# CR78-MB.net
KiCad netlist of a schematic drawn in EAGLE
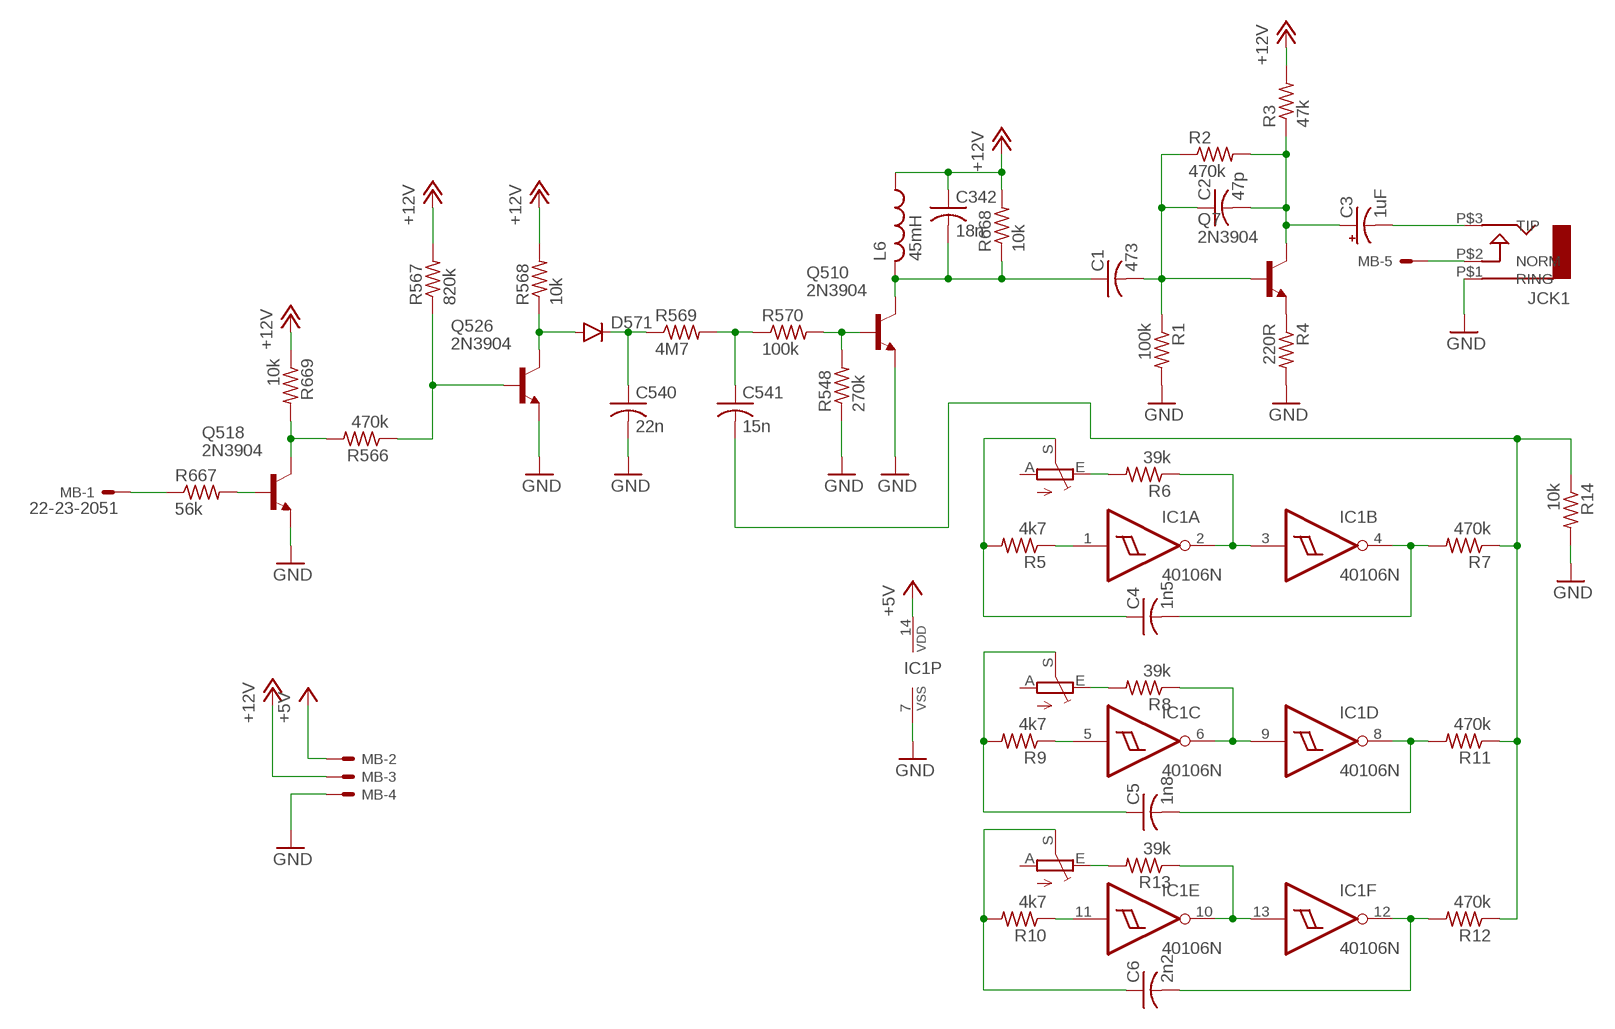
[diagram p0: schematic, sheet 1]

(export (version "E")
  (design (tool "Eeschema 10.0.6"))
  (components
    (comp (ref "C1")
      (value "473")
      (footprint "eagle-import:C050-025X075")
      (libsource (lib "eagle-import") (part "C-US050-025X075"))
    )
    (comp (ref "C2")
      (value "47p")
      (footprint "eagle-import:C025-030X050")
      (libsource (lib "eagle-import") (part "C-US025-030X050"))
    )
    (comp (ref "C3")
      (value "1uF")
      (footprint "eagle-import:B45181B")
      (libsource (lib "eagle-import") (part "CPOL-USB45181B"))
    )
    (comp (ref "C4")
      (value "1n5")
      (footprint "eagle-import:C050-025X075")
      (libsource (lib "eagle-import") (part "C-US050-025X075"))
    )
    (comp (ref "C5")
      (value "1n8")
      (footprint "eagle-import:C050-025X075")
      (libsource (lib "eagle-import") (part "C-US050-025X075"))
    )
    (comp (ref "C6")
      (value "2n2")
      (footprint "eagle-import:C050-025X075")
      (libsource (lib "eagle-import") (part "C-US050-025X075"))
    )
    (comp (ref "C342")
      (value "18n")
      (footprint "eagle-import:C050-025X075")
      (libsource (lib "eagle-import") (part "C-US050-025X075"))
    )
    (comp (ref "C540")
      (value "22n")
      (footprint "eagle-import:C050-025X075")
      (libsource (lib "eagle-import") (part "C-US050-025X075"))
    )
    (comp (ref "C541")
      (value "15n")
      (footprint "eagle-import:C050-025X075")
      (libsource (lib "eagle-import") (part "C-US050-025X075"))
    )
    (comp (ref "D571")
      (value "DIODE1N4148")
      (footprint "eagle-import:DIODE-1N4148")
      (libsource (lib "eagle-import") (part "DIODE1N4148"))
    )
    (comp (ref "IC1")
      (value "40106N")
      (footprint "eagle-import:DIL14")
      (libsource (lib "eagle-import") (part "40106N"))
    )
    (comp (ref "JCK1")
      (value "AUDIO-JACK")
      (footprint "eagle-import:ERTHENVAR-JACK-90DEG")
      (libsource (lib "eagle-import") (part "AUDIO-JACK"))
    )
    (comp (ref "L6")
      (value "45mH")
      (footprint "eagle-import:0204_5")
      (libsource (lib "eagle-import") (part "L-US0204/5"))
    )
    (comp (ref "MB")
      (value "22-23-2051")
      (footprint "eagle-import:22-23-2051")
      (fields (field (name "MF") "MOLEX"))
      (libsource (lib "eagle-import") (part "22-23-2051"))
    )
    (comp (ref "Q7")
      (value "2N3904")
      (footprint "eagle-import:TO92")
      (libsource (lib "eagle-import") (part "2N3904"))
    )
    (comp (ref "Q510")
      (value "2N3904")
      (footprint "eagle-import:TO92")
      (libsource (lib "eagle-import") (part "2N3904"))
    )
    (comp (ref "Q518")
      (value "2N3904")
      (footprint "eagle-import:TO92")
      (libsource (lib "eagle-import") (part "2N3904"))
    )
    (comp (ref "Q526")
      (value "2N3904")
      (footprint "eagle-import:TO92")
      (libsource (lib "eagle-import") (part "2N3904"))
    )
    (comp (ref "R1")
      (value "100k")
      (footprint "eagle-import:0207_7")
      (libsource (lib "eagle-import") (part "R-US_0207/7"))
    )
    (comp (ref "R2")
      (value "470k")
      (footprint "eagle-import:0207_7")
      (libsource (lib "eagle-import") (part "R-US_0207/7"))
    )
    (comp (ref "R3")
      (value "47k")
      (footprint "eagle-import:0207_7")
      (libsource (lib "eagle-import") (part "R-US_0207/7"))
    )
    (comp (ref "R4")
      (value "220R")
      (footprint "eagle-import:0207_7")
      (libsource (lib "eagle-import") (part "R-US_0207/7"))
    )
    (comp (ref "R5")
      (value "4k7")
      (footprint "eagle-import:0207_7")
      (libsource (lib "eagle-import") (part "R-US_0207/7"))
    )
    (comp (ref "R6")
      (value "39k")
      (footprint "eagle-import:0207_7")
      (libsource (lib "eagle-import") (part "R-US_0207/7"))
    )
    (comp (ref "R7")
      (value "470k")
      (footprint "eagle-import:0207_7")
      (libsource (lib "eagle-import") (part "R-US_0207/7"))
    )
    (comp (ref "R8")
      (value "39k")
      (footprint "eagle-import:0207_7")
      (libsource (lib "eagle-import") (part "R-US_0207/7"))
    )
    (comp (ref "R9")
      (value "4k7")
      (footprint "eagle-import:0207_7")
      (libsource (lib "eagle-import") (part "R-US_0207/7"))
    )
    (comp (ref "R10")
      (value "4k7")
      (footprint "eagle-import:0207_7")
      (libsource (lib "eagle-import") (part "R-US_0207/7"))
    )
    (comp (ref "R11")
      (value "470k")
      (footprint "eagle-import:0207_7")
      (libsource (lib "eagle-import") (part "R-US_0207/7"))
    )
    (comp (ref "R12")
      (value "470k")
      (footprint "eagle-import:0207_7")
      (libsource (lib "eagle-import") (part "R-US_0207/7"))
    )
    (comp (ref "R13")
      (value "39k")
      (footprint "eagle-import:0207_7")
      (libsource (lib "eagle-import") (part "R-US_0207/7"))
    )
    (comp (ref "R14")
      (value "10k")
      (footprint "eagle-import:0207_7")
      (libsource (lib "eagle-import") (part "R-US_0207/7"))
    )
    (comp (ref "R548")
      (value "270k")
      (footprint "eagle-import:0207_7")
      (libsource (lib "eagle-import") (part "R-US_0207/7"))
    )
    (comp (ref "R566")
      (value "470k")
      (footprint "eagle-import:0207_7")
      (libsource (lib "eagle-import") (part "R-US_0207/7"))
    )
    (comp (ref "R567")
      (value "820k")
      (footprint "eagle-import:0207_7")
      (libsource (lib "eagle-import") (part "R-US_0207/7"))
    )
    (comp (ref "R568")
      (value "10k")
      (footprint "eagle-import:0207_7")
      (libsource (lib "eagle-import") (part "R-US_0207/7"))
    )
    (comp (ref "R569")
      (value "4M7")
      (footprint "eagle-import:0207_7")
      (libsource (lib "eagle-import") (part "R-US_0207/7"))
    )
    (comp (ref "R570")
      (value "100k")
      (footprint "eagle-import:0207_7")
      (libsource (lib "eagle-import") (part "R-US_0207/7"))
    )
    (comp (ref "R667")
      (value "56k")
      (footprint "eagle-import:0207_7")
      (libsource (lib "eagle-import") (part "R-US_0207/7"))
    )
    (comp (ref "R668")
      (value "10k")
      (footprint "eagle-import:0207_7")
      (libsource (lib "eagle-import") (part "R-US_0207/7"))
    )
    (comp (ref "R669")
      (value "10k")
      (footprint "eagle-import:0207_7")
      (libsource (lib "eagle-import") (part "R-US_0207/7"))
    )
    (comp (ref "VR1")
      (value "20K")
      (footprint "eagle-import:B64Y")
      (libsource (lib "eagle-import") (part "TRIM_EU-B64Y"))
    )
    (comp (ref "VR2")
      (value "20K")
      (footprint "eagle-import:B64Y")
      (libsource (lib "eagle-import") (part "TRIM_EU-B64Y"))
    )
    (comp (ref "VR3")
      (value "20K")
      (footprint "eagle-import:B64Y")
      (libsource (lib "eagle-import") (part "TRIM_EU-B64Y"))
    )
  )
  (nets
    (net (code "1") (name "+5V") (class "Default")
      (node (ref "IC1") (pin "14") (pinfunction "VDD_14") (pintype "power_in"))
      (node (ref "MB") (pin "2") (pinfunction "S_2") (pintype "passive"))
    )
    (net (code "2") (name "+12V") (class "Default")
      (node (ref "C342") (pin "1") (pinfunction "1_1") (pintype "passive"))
      (node (ref "L6") (pin "1") (pinfunction "1_1") (pintype "passive"))
      (node (ref "MB") (pin "3") (pinfunction "S_3") (pintype "passive"))
      (node (ref "R3") (pin "2") (pinfunction "2_2") (pintype "passive"))
      (node (ref "R567") (pin "2") (pinfunction "2_2") (pintype "passive"))
      (node (ref "R568") (pin "2") (pinfunction "2_2") (pintype "passive"))
      (node (ref "R668") (pin "2") (pinfunction "2_2") (pintype "passive"))
      (node (ref "R669") (pin "1") (pinfunction "1_1") (pintype "passive"))
    )
    (net (code "3") (name "GND") (class "Default")
      (node (ref "C540") (pin "2") (pinfunction "2_2") (pintype "passive"))
      (node (ref "IC1") (pin "7") (pinfunction "VSS_7") (pintype "power_in"))
      (node (ref "JCK1") (pin "P$1") (pinfunction "RING_P$1") (pintype "bidirectional"))
      (node (ref "MB") (pin "4") (pinfunction "S_4") (pintype "passive"))
      (node (ref "Q510") (pin "3") (pinfunction "E_3") (pintype "passive"))
      (node (ref "Q518") (pin "3") (pinfunction "E_3") (pintype "passive"))
      (node (ref "Q526") (pin "3") (pinfunction "E_3") (pintype "passive"))
      (node (ref "R1") (pin "2") (pinfunction "2_2") (pintype "passive"))
      (node (ref "R14") (pin "2") (pinfunction "2_2") (pintype "passive"))
      (node (ref "R4") (pin "2") (pinfunction "2_2") (pintype "passive"))
      (node (ref "R548") (pin "1") (pinfunction "1_1") (pintype "passive"))
    )
    (net (code "4") (name "Net-(C4-Pad1)") (class "Default")
      (node (ref "C4") (pin "1") (pinfunction "1_1") (pintype "passive"))
      (node (ref "R5") (pin "2") (pinfunction "2_2") (pintype "passive"))
      (node (ref "VR1") (pin "S") (pinfunction "S_S") (pintype "passive"))
    )
    (net (code "5") (name "Net-(C5-Pad1)") (class "Default")
      (node (ref "C5") (pin "1") (pinfunction "1_1") (pintype "passive"))
      (node (ref "R9") (pin "2") (pinfunction "2_2") (pintype "passive"))
      (node (ref "VR2") (pin "S") (pinfunction "S_S") (pintype "passive"))
    )
    (net (code "6") (name "Net-(C6-Pad1)") (class "Default")
      (node (ref "C6") (pin "1") (pinfunction "1_1") (pintype "passive"))
      (node (ref "R10") (pin "2") (pinfunction "2_2") (pintype "passive"))
      (node (ref "VR3") (pin "S") (pinfunction "S_S") (pintype "passive"))
    )
    (net (code "7") (name "Net-(C540-Pad1)") (class "Default")
      (node (ref "C540") (pin "1") (pinfunction "1_1") (pintype "passive"))
      (node (ref "D571") (pin "C") (pinfunction "C_C") (pintype "passive"))
      (node (ref "R569") (pin "1") (pinfunction "1_1") (pintype "passive"))
    )
    (net (code "8") (name "Net-(C541-Pad1)") (class "Default")
      (node (ref "C541") (pin "1") (pinfunction "1_1") (pintype "passive"))
      (node (ref "R569") (pin "2") (pinfunction "2_2") (pintype "passive"))
      (node (ref "R570") (pin "1") (pinfunction "1_1") (pintype "passive"))
    )
    (net (code "9") (name "Net-(C541-Pad2)") (class "Default")
      (node (ref "C541") (pin "2") (pinfunction "2_2") (pintype "passive"))
      (node (ref "R11") (pin "1") (pinfunction "1_1") (pintype "passive"))
      (node (ref "R12") (pin "1") (pinfunction "1_1") (pintype "passive"))
      (node (ref "R14") (pin "1") (pinfunction "1_1") (pintype "passive"))
      (node (ref "R7") (pin "1") (pinfunction "1_1") (pintype "passive"))
    )
    (net (code "10") (name "Net-(IC1A-I)") (class "Default")
      (node (ref "IC1") (pin "1") (pinfunction "I_1") (pintype "input"))
      (node (ref "R5") (pin "1") (pinfunction "1_1") (pintype "passive"))
    )
    (net (code "11") (name "Net-(IC1A-O)") (class "Default")
      (node (ref "IC1") (pin "2") (pinfunction "O_2") (pintype "output"))
      (node (ref "IC1") (pin "3") (pinfunction "I_3") (pintype "input"))
      (node (ref "R6") (pin "1") (pinfunction "1_1") (pintype "passive"))
    )
    (net (code "12") (name "Net-(IC1B-O)") (class "Default")
      (node (ref "C4") (pin "2") (pinfunction "2_2") (pintype "passive"))
      (node (ref "IC1") (pin "4") (pinfunction "O_4") (pintype "output"))
      (node (ref "R7") (pin "2") (pinfunction "2_2") (pintype "passive"))
    )
    (net (code "13") (name "Net-(IC1C-I)") (class "Default")
      (node (ref "IC1") (pin "5") (pinfunction "I_5") (pintype "input"))
      (node (ref "R9") (pin "1") (pinfunction "1_1") (pintype "passive"))
    )
    (net (code "14") (name "Net-(IC1C-O)") (class "Default")
      (node (ref "IC1") (pin "6") (pinfunction "O_6") (pintype "output"))
      (node (ref "IC1") (pin "9") (pinfunction "I_9") (pintype "input"))
      (node (ref "R8") (pin "1") (pinfunction "1_1") (pintype "passive"))
    )
    (net (code "15") (name "Net-(IC1D-O)") (class "Default")
      (node (ref "C5") (pin "2") (pinfunction "2_2") (pintype "passive"))
      (node (ref "IC1") (pin "8") (pinfunction "O_8") (pintype "output"))
      (node (ref "R11") (pin "2") (pinfunction "2_2") (pintype "passive"))
    )
    (net (code "16") (name "Net-(IC1E-I)") (class "Default")
      (node (ref "IC1") (pin "11") (pinfunction "I_11") (pintype "input"))
      (node (ref "R10") (pin "1") (pinfunction "1_1") (pintype "passive"))
    )
    (net (code "17") (name "Net-(IC1E-O)") (class "Default")
      (node (ref "IC1") (pin "10") (pinfunction "O_10") (pintype "output"))
      (node (ref "IC1") (pin "13") (pinfunction "I_13") (pintype "input"))
      (node (ref "R13") (pin "1") (pinfunction "1_1") (pintype "passive"))
    )
    (net (code "18") (name "Net-(IC1F-O)") (class "Default")
      (node (ref "C6") (pin "2") (pinfunction "2_2") (pintype "passive"))
      (node (ref "IC1") (pin "12") (pinfunction "O_12") (pintype "output"))
      (node (ref "R12") (pin "2") (pinfunction "2_2") (pintype "passive"))
    )
    (net (code "19") (name "Net-(JCK1-NORM)") (class "Default")
      (node (ref "JCK1") (pin "P$2") (pinfunction "NORM_P$2") (pintype "bidirectional"))
      (node (ref "MB") (pin "5") (pinfunction "S_5") (pintype "passive"))
    )
    (net (code "20") (name "Net-(JCK1-TIP)") (class "Default")
      (node (ref "C3") (pin "-") (pinfunction "-_-") (pintype "passive"))
      (node (ref "JCK1") (pin "P$3") (pinfunction "TIP_P$3") (pintype "bidirectional"))
    )
    (net (code "21") (name "Net-(MBA-S)") (class "Default")
      (node (ref "MB") (pin "1") (pinfunction "S_1") (pintype "passive"))
      (node (ref "R667") (pin "1") (pinfunction "1_1") (pintype "passive"))
    )
    (net (code "22") (name "Net-(Q7-B)") (class "Default")
      (node (ref "C1") (pin "2") (pinfunction "2_2") (pintype "passive"))
      (node (ref "C2") (pin "1") (pinfunction "1_1") (pintype "passive"))
      (node (ref "Q7") (pin "2") (pinfunction "B_2") (pintype "passive"))
      (node (ref "R1") (pin "1") (pinfunction "1_1") (pintype "passive"))
      (node (ref "R2") (pin "1") (pinfunction "1_1") (pintype "passive"))
    )
    (net (code "23") (name "Net-(Q7-C)") (class "Default")
      (node (ref "C2") (pin "2") (pinfunction "2_2") (pintype "passive"))
      (node (ref "C3") (pin "+") (pinfunction "+_+") (pintype "passive"))
      (node (ref "Q7") (pin "1") (pinfunction "C_1") (pintype "passive"))
      (node (ref "R2") (pin "2") (pinfunction "2_2") (pintype "passive"))
      (node (ref "R3") (pin "1") (pinfunction "1_1") (pintype "passive"))
    )
    (net (code "24") (name "Net-(Q7-E)") (class "Default")
      (node (ref "Q7") (pin "3") (pinfunction "E_3") (pintype "passive"))
      (node (ref "R4") (pin "1") (pinfunction "1_1") (pintype "passive"))
    )
    (net (code "25") (name "Net-(Q510-B)") (class "Default")
      (node (ref "Q510") (pin "2") (pinfunction "B_2") (pintype "passive"))
      (node (ref "R548") (pin "2") (pinfunction "2_2") (pintype "passive"))
      (node (ref "R570") (pin "2") (pinfunction "2_2") (pintype "passive"))
    )
    (net (code "26") (name "Net-(Q510-C)") (class "Default")
      (node (ref "C1") (pin "1") (pinfunction "1_1") (pintype "passive"))
      (node (ref "C342") (pin "2") (pinfunction "2_2") (pintype "passive"))
      (node (ref "L6") (pin "2") (pinfunction "2_2") (pintype "passive"))
      (node (ref "Q510") (pin "1") (pinfunction "C_1") (pintype "passive"))
      (node (ref "R668") (pin "1") (pinfunction "1_1") (pintype "passive"))
    )
    (net (code "27") (name "Net-(Q518-B)") (class "Default")
      (node (ref "Q518") (pin "2") (pinfunction "B_2") (pintype "passive"))
      (node (ref "R667") (pin "2") (pinfunction "2_2") (pintype "passive"))
    )
    (net (code "28") (name "Net-(Q518-C)") (class "Default")
      (node (ref "Q518") (pin "1") (pinfunction "C_1") (pintype "passive"))
      (node (ref "R566") (pin "2") (pinfunction "2_2") (pintype "passive"))
      (node (ref "R669") (pin "2") (pinfunction "2_2") (pintype "passive"))
    )
    (net (code "29") (name "Net-(Q526-B)") (class "Default")
      (node (ref "Q526") (pin "2") (pinfunction "B_2") (pintype "passive"))
      (node (ref "R566") (pin "1") (pinfunction "1_1") (pintype "passive"))
      (node (ref "R567") (pin "1") (pinfunction "1_1") (pintype "passive"))
    )
    (net (code "30") (name "Net-(Q526-C)") (class "Default")
      (node (ref "D571") (pin "A") (pinfunction "A_A") (pintype "passive"))
      (node (ref "Q526") (pin "1") (pinfunction "C_1") (pintype "passive"))
      (node (ref "R568") (pin "1") (pinfunction "1_1") (pintype "passive"))
    )
    (net (code "31") (name "Net-(R6-Pad2)") (class "Default")
      (node (ref "R6") (pin "2") (pinfunction "2_2") (pintype "passive"))
      (node (ref "VR1") (pin "E") (pinfunction "E_E") (pintype "passive"))
    )
    (net (code "32") (name "Net-(R8-Pad2)") (class "Default")
      (node (ref "R8") (pin "2") (pinfunction "2_2") (pintype "passive"))
      (node (ref "VR2") (pin "E") (pinfunction "E_E") (pintype "passive"))
    )
    (net (code "33") (name "Net-(R13-Pad2)") (class "Default")
      (node (ref "R13") (pin "2") (pinfunction "2_2") (pintype "passive"))
      (node (ref "VR3") (pin "E") (pinfunction "E_E") (pintype "passive"))
    )
    (net (code "34") (name "unconnected-(VR1-PadA)") (class "Default")
      (node (ref "VR1") (pin "A") (pinfunction "A_A") (pintype "passive"))
    )
    (net (code "35") (name "unconnected-(VR2-PadA)") (class "Default")
      (node (ref "VR2") (pin "A") (pinfunction "A_A") (pintype "passive"))
    )
    (net (code "36") (name "unconnected-(VR3-PadA)") (class "Default")
      (node (ref "VR3") (pin "A") (pinfunction "A_A") (pintype "passive"))
    )
  )
)
